# 608_donkey_030102_AllDirections.net
KiCad netlist of a schematic drawn in EAGLE
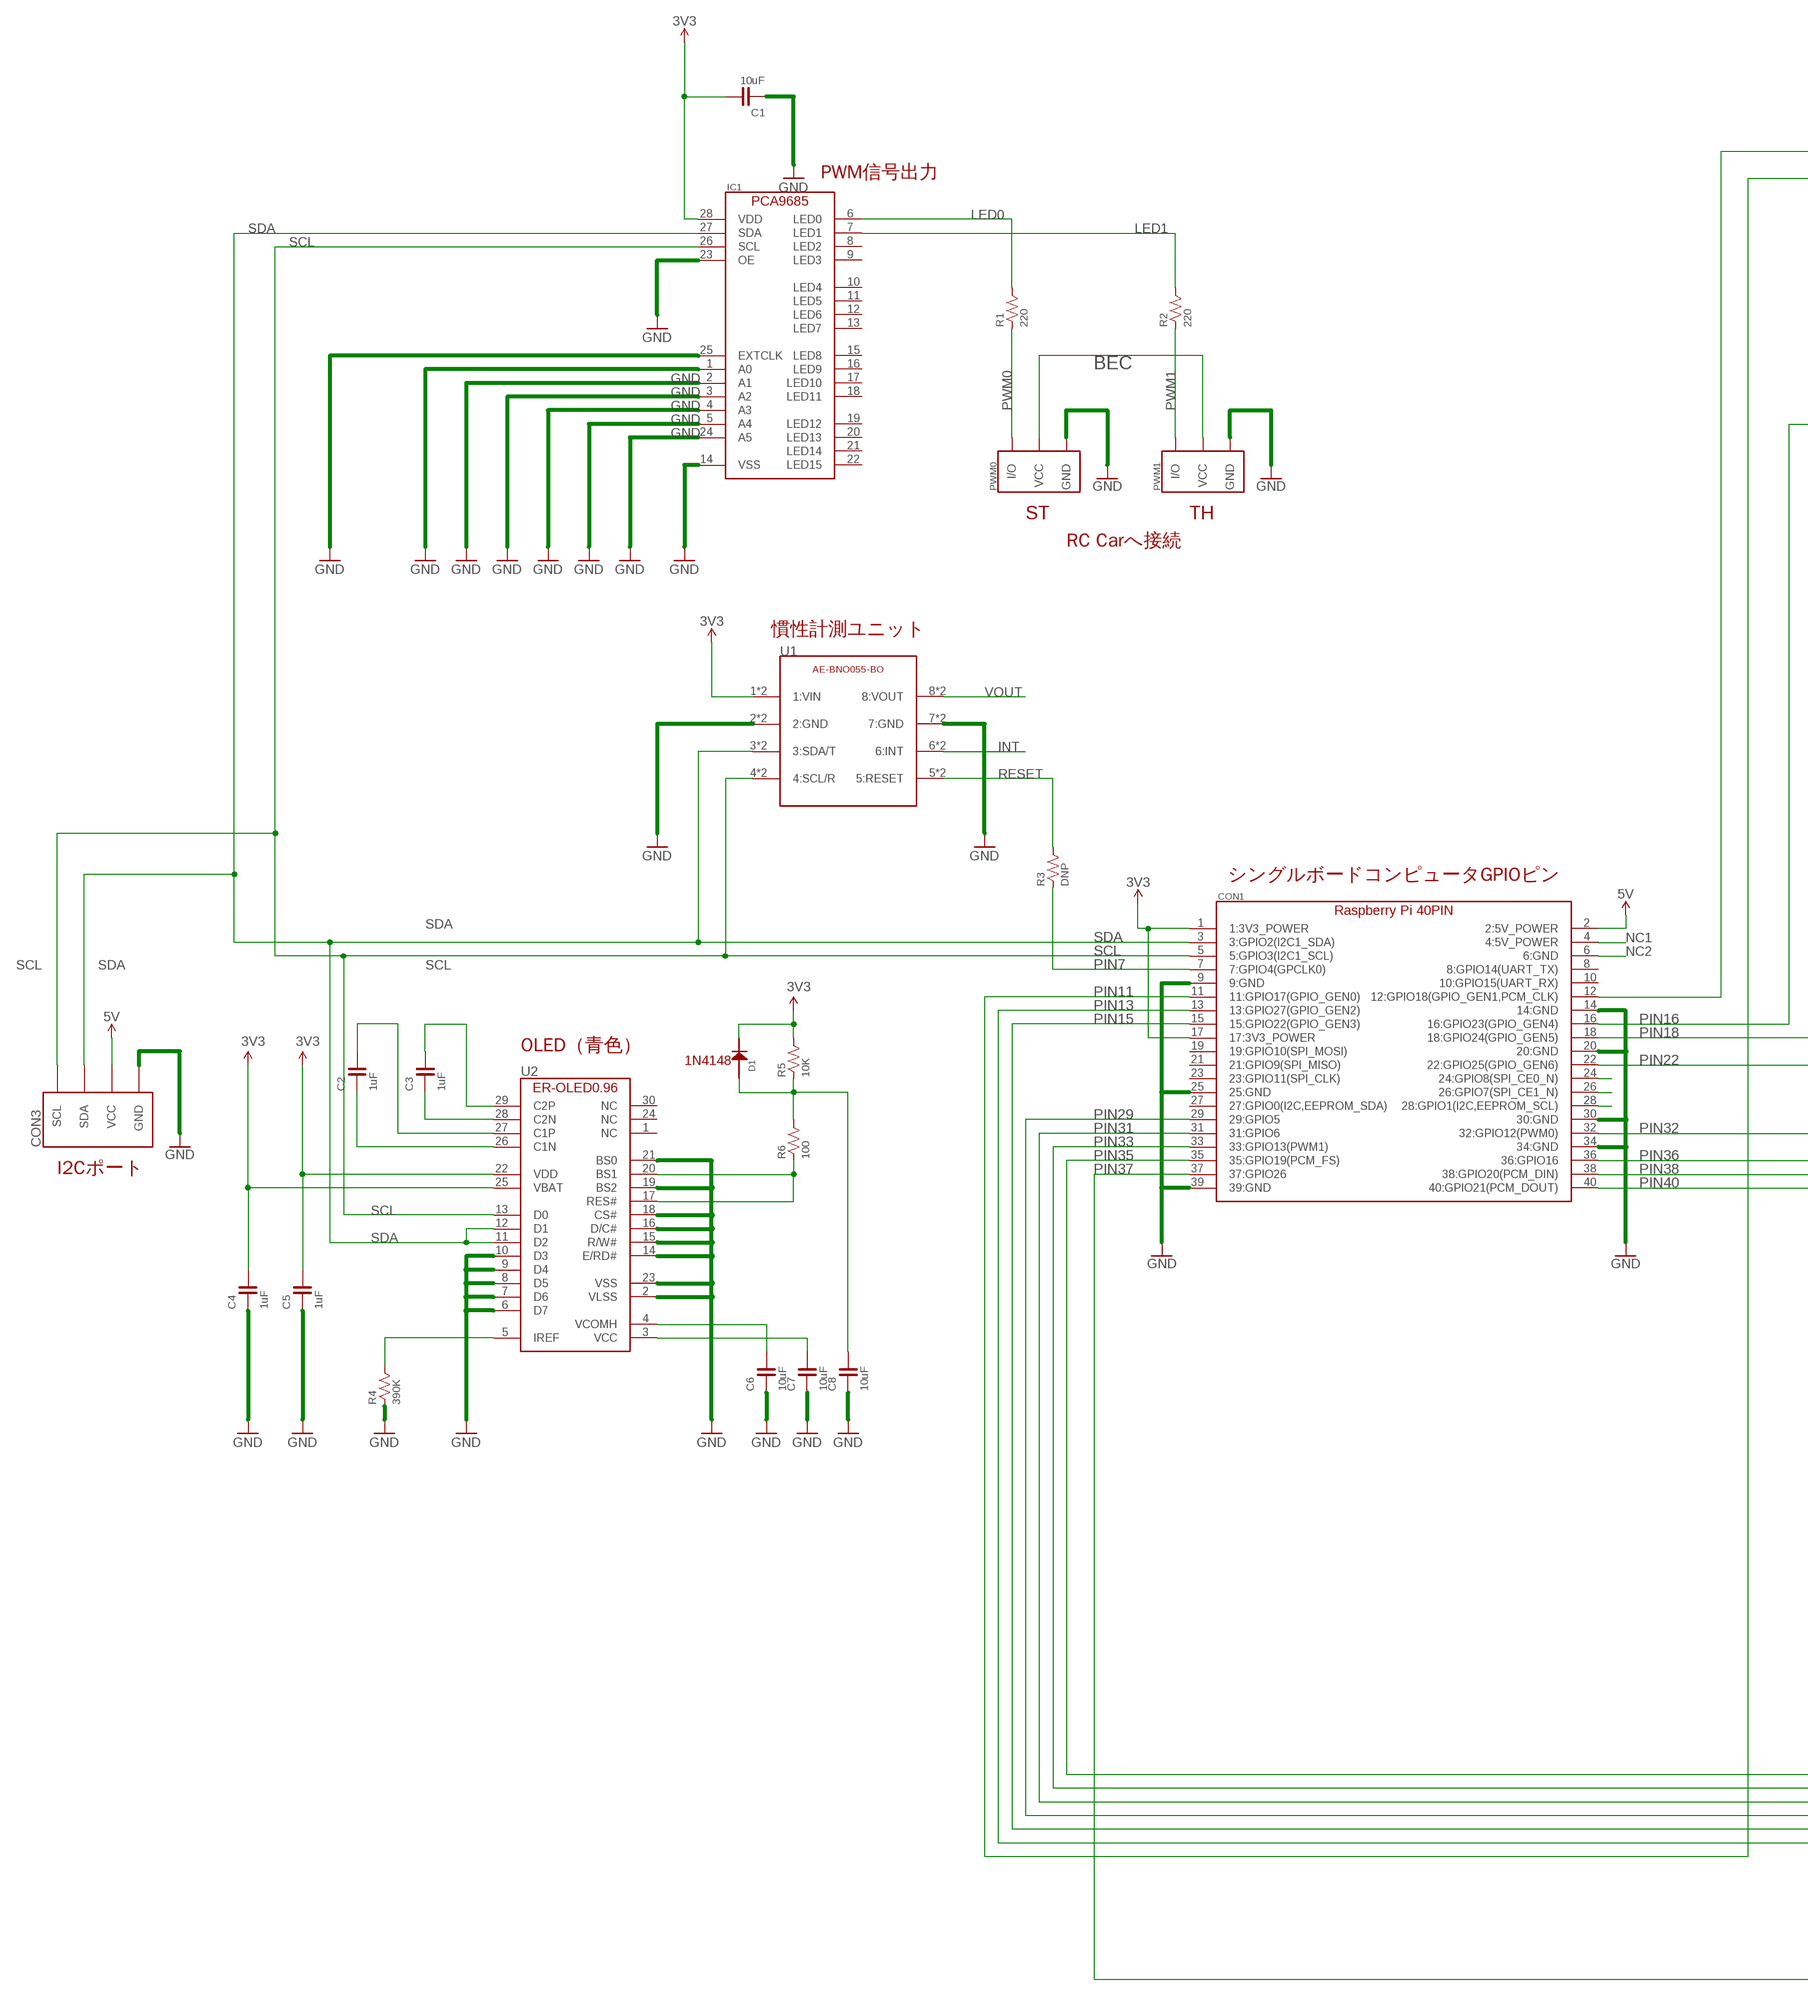
[diagram p0: schematic, sheet 1, part 1 of 3]
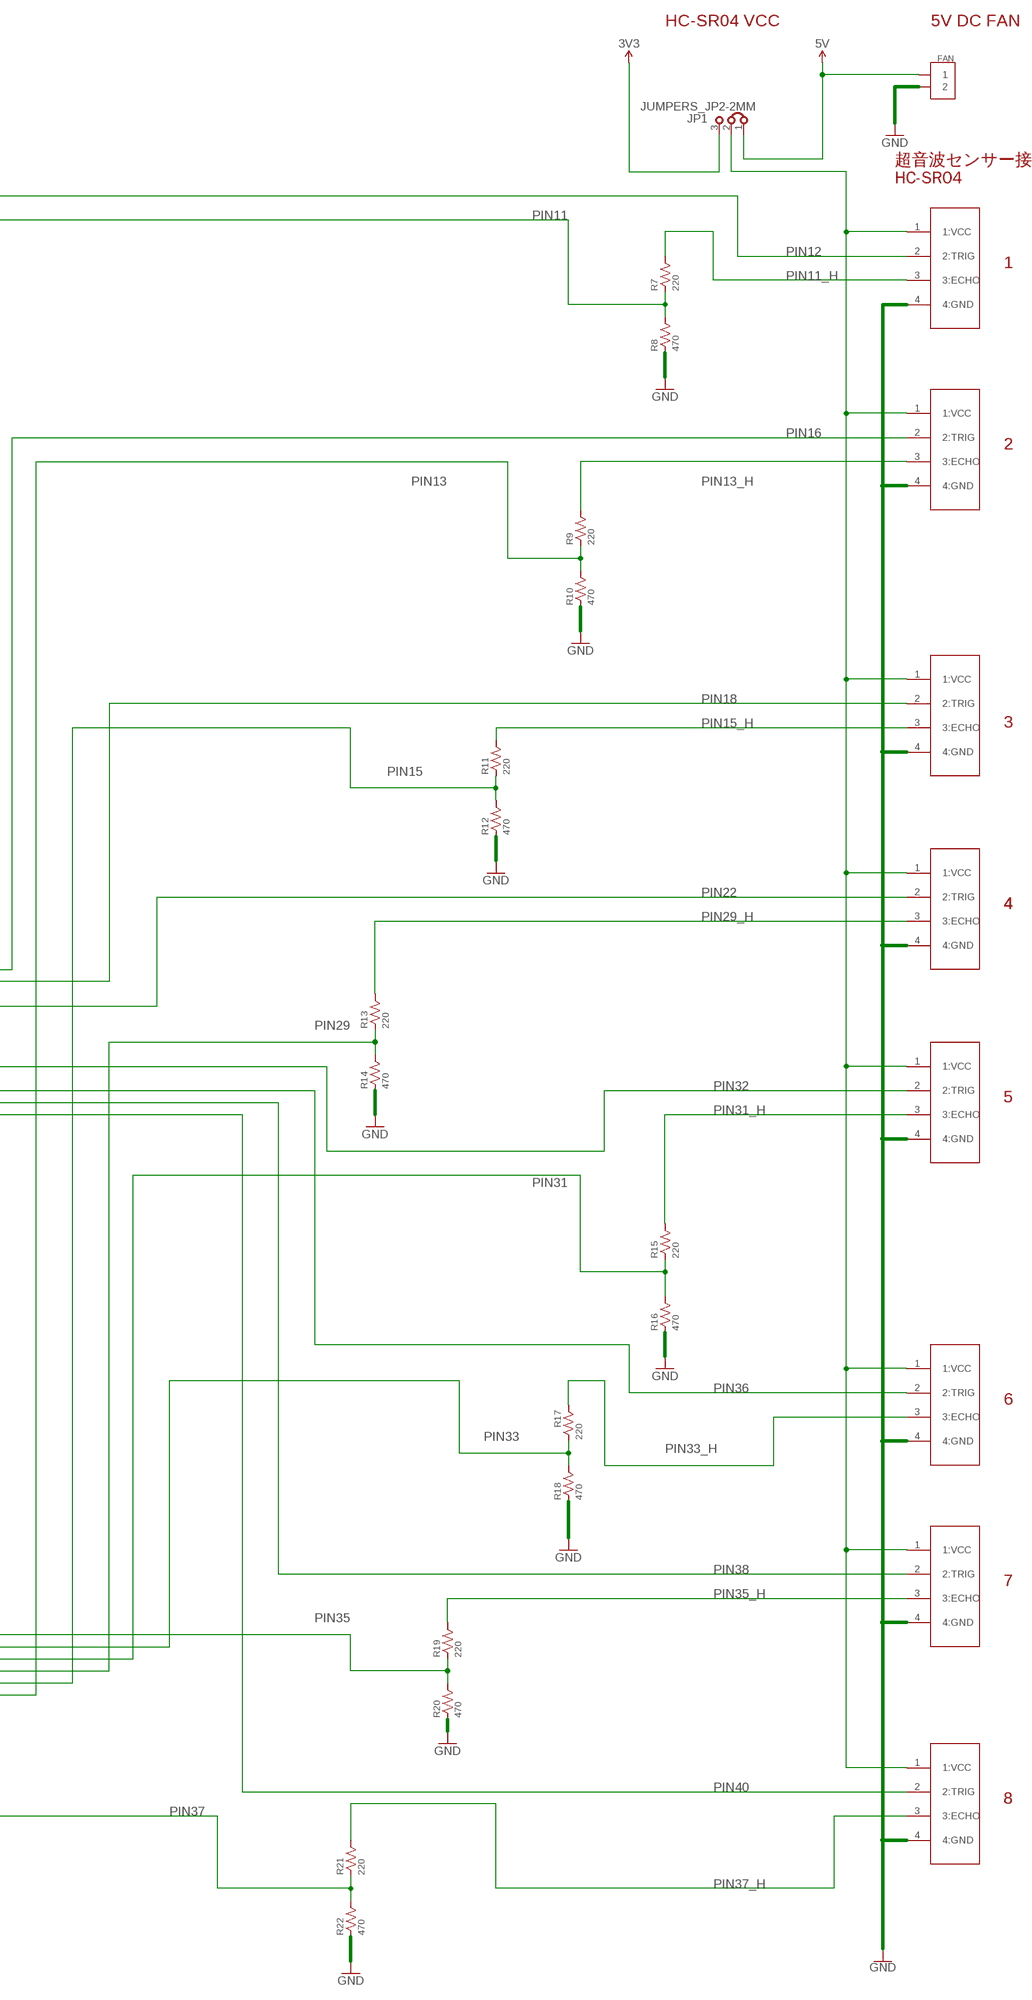
[diagram p1: schematic, sheet 1, part 2 of 3]
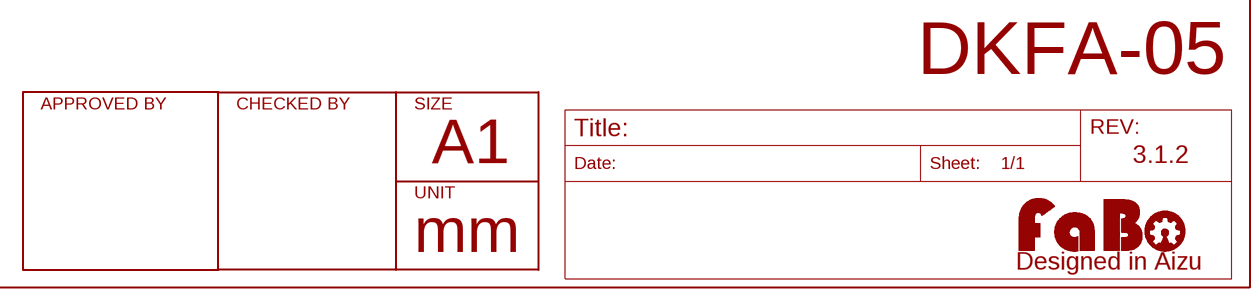
[diagram p2: schematic, sheet 1, part 3 of 3]

(export (version "E")
  (design (tool "Eeschema 10.0.6"))
  (components
    (comp (ref "C1")
      (value "10uF")
      (footprint "eagle-import:0603")
      (libsource (lib "eagle-import") (part "CAPACITOR-0603"))
    )
    (comp (ref "C2")
      (value "1uF")
      (footprint "eagle-import:0603-BOTTOM")
      (libsource (lib "eagle-import") (part "CAPACITOR-0603-BOTTOM"))
    )
    (comp (ref "C3")
      (value "1uF")
      (footprint "eagle-import:0603-BOTTOM")
      (libsource (lib "eagle-import") (part "CAPACITOR-0603-BOTTOM"))
    )
    (comp (ref "C4")
      (value "1uF")
      (footprint "eagle-import:0603-BOTTOM")
      (libsource (lib "eagle-import") (part "CAPACITOR-0603-BOTTOM"))
    )
    (comp (ref "C5")
      (value "1uF")
      (footprint "eagle-import:0603-BOTTOM")
      (libsource (lib "eagle-import") (part "CAPACITOR-0603-BOTTOM"))
    )
    (comp (ref "C6")
      (value "10uF")
      (footprint "eagle-import:0603-BOTTOM")
      (libsource (lib "eagle-import") (part "CAPACITOR-0603-BOTTOM"))
    )
    (comp (ref "C7")
      (value "10uF")
      (footprint "eagle-import:0603-BOTTOM")
      (libsource (lib "eagle-import") (part "CAPACITOR-0603-BOTTOM"))
    )
    (comp (ref "C8")
      (value "10uF")
      (footprint "eagle-import:0603-BOTTOM")
      (libsource (lib "eagle-import") (part "CAPACITOR-0603-BOTTOM"))
    )
    (comp (ref "CON1")
      (value "RASPBERRYPI_SHEILD")
      (footprint "eagle-import:RASPBERRY_PI_SHILED")
      (libsource (lib "eagle-import") (part "RASPBERRYPI_SHEILD"))
    )
    (comp (ref "CON3")
      (value "FABO_BRICK_I2C-S04B-PASK-2")
      (footprint "eagle-import:FABO_BRICK_I2C_S04B-PASK-2")
      (libsource (lib "eagle-import") (part "FABO_BRICK_I2C-S04B-PASK-2"))
    )
    (comp (ref "D1")
      (value "1N4148")
      (footprint "eagle-import:1N4148W")
      (libsource (lib "eagle-import") (part "1N4148"))
    )
    (comp (ref "FAN")
      (value "PIN_1X2")
      (footprint "eagle-import:PIN_1X2")
      (libsource (lib "eagle-import") (part "PIN_1X2"))
    )
    (comp (ref "HC1")
      (value "HC-SR04CONHS-SR04CON-SPEACING")
      (footprint "eagle-import:HC-SR04CON-SPEACE")
      (libsource (lib "eagle-import") (part "HC-SR04CONHS-SR04CON-SPEACING"))
    )
    (comp (ref "HC2")
      (value "HC-SR04CONHS-SR04CON-SPEACING")
      (footprint "eagle-import:HC-SR04CON-SPEACE")
      (libsource (lib "eagle-import") (part "HC-SR04CONHS-SR04CON-SPEACING"))
    )
    (comp (ref "HC3")
      (value "HC-SR04CONHS-SR04CON-SPEACING")
      (footprint "eagle-import:HC-SR04CON-SPEACE")
      (libsource (lib "eagle-import") (part "HC-SR04CONHS-SR04CON-SPEACING"))
    )
    (comp (ref "HC4")
      (value "HC-SR04CONHS-SR04CON-SPEACING")
      (footprint "eagle-import:HC-SR04CON-SPEACE")
      (libsource (lib "eagle-import") (part "HC-SR04CONHS-SR04CON-SPEACING"))
    )
    (comp (ref "HC5")
      (value "HC-SR04CONHS-SR04CON-SPEACING")
      (footprint "eagle-import:HC-SR04CON-SPEACE")
      (libsource (lib "eagle-import") (part "HC-SR04CONHS-SR04CON-SPEACING"))
    )
    (comp (ref "HC6")
      (value "HC-SR04CONHS-SR04CON-SPEACING")
      (footprint "eagle-import:HC-SR04CON-SPEACE")
      (libsource (lib "eagle-import") (part "HC-SR04CONHS-SR04CON-SPEACING"))
    )
    (comp (ref "HC7")
      (value "HC-SR04CONHS-SR04CON-SPEACING")
      (footprint "eagle-import:HC-SR04CON-SPEACE")
      (libsource (lib "eagle-import") (part "HC-SR04CONHS-SR04CON-SPEACING"))
    )
    (comp (ref "HC8")
      (value "HC-SR04CONHS-SR04CON-SPEACING")
      (footprint "eagle-import:HC-SR04CON-SPEACE")
      (libsource (lib "eagle-import") (part "HC-SR04CONHS-SR04CON-SPEACING"))
    )
    (comp (ref "IC1")
      (value "PCA9685BS")
      (footprint "eagle-import:PCA9685")
      (libsource (lib "eagle-import") (part "PCA9685BS"))
    )
    (comp (ref "JP1")
      (value "JUMPERS_JP2-2MM")
      (footprint "eagle-import:JUMPERS_JP2-2MM")
      (libsource (lib "eagle-import") (part "JUMPERS_JP2-2MM"))
    )
    (comp (ref "LOGO1")
      (value "LOGO_FABO-M")
      (footprint "eagle-import:LOGO_FABO_M")
      (libsource (lib "eagle-import") (part "LOGO_FABO-M"))
    )
    (comp (ref "PWM0")
      (value "PWM0")
      (footprint "eagle-import:PIN_1X3_NARROW")
      (libsource (lib "eagle-import") (part "FABO-BRICK-3PIN_HEADER"))
    )
    (comp (ref "PWM1")
      (value "PWM1")
      (footprint "eagle-import:PIN_1X3_NARROW")
      (libsource (lib "eagle-import") (part "FABO-BRICK-3PIN_HEADER"))
    )
    (comp (ref "R1")
      (value "220")
      (footprint "eagle-import:0603")
      (libsource (lib "eagle-import") (part "RESISTOR-0603"))
    )
    (comp (ref "R2")
      (value "220")
      (footprint "eagle-import:0603")
      (libsource (lib "eagle-import") (part "RESISTOR-0603"))
    )
    (comp (ref "R3")
      (value "DNP")
      (footprint "eagle-import:0603-BOTTOM")
      (libsource (lib "eagle-import") (part "RESISTOR-0603-BOTTOM"))
    )
    (comp (ref "R4")
      (value "390K")
      (footprint "eagle-import:0603-BOTTOM")
      (libsource (lib "eagle-import") (part "RESISTOR-0603-BOTTOM"))
    )
    (comp (ref "R5")
      (value "10K")
      (footprint "eagle-import:0603-BOTTOM")
      (libsource (lib "eagle-import") (part "RESISTOR-0603-BOTTOM"))
    )
    (comp (ref "R6")
      (value "100")
      (footprint "eagle-import:0603-BOTTOM")
      (libsource (lib "eagle-import") (part "RESISTOR-0603-BOTTOM"))
    )
    (comp (ref "R7")
      (value "220")
      (footprint "eagle-import:0603")
      (libsource (lib "eagle-import") (part "RESISTOR-0603"))
    )
    (comp (ref "R8")
      (value "470")
      (footprint "eagle-import:0603")
      (libsource (lib "eagle-import") (part "RESISTOR-0603"))
    )
    (comp (ref "R9")
      (value "220")
      (footprint "eagle-import:0603")
      (libsource (lib "eagle-import") (part "RESISTOR-0603"))
    )
    (comp (ref "R10")
      (value "470")
      (footprint "eagle-import:0603")
      (libsource (lib "eagle-import") (part "RESISTOR-0603"))
    )
    (comp (ref "R11")
      (value "220")
      (footprint "eagle-import:0603")
      (libsource (lib "eagle-import") (part "RESISTOR-0603"))
    )
    (comp (ref "R12")
      (value "470")
      (footprint "eagle-import:0603")
      (libsource (lib "eagle-import") (part "RESISTOR-0603"))
    )
    (comp (ref "R13")
      (value "220")
      (footprint "eagle-import:0603")
      (libsource (lib "eagle-import") (part "RESISTOR-0603"))
    )
    (comp (ref "R14")
      (value "470")
      (footprint "eagle-import:0603")
      (libsource (lib "eagle-import") (part "RESISTOR-0603"))
    )
    (comp (ref "R15")
      (value "220")
      (footprint "eagle-import:0603")
      (libsource (lib "eagle-import") (part "RESISTOR-0603"))
    )
    (comp (ref "R16")
      (value "470")
      (footprint "eagle-import:0603")
      (libsource (lib "eagle-import") (part "RESISTOR-0603"))
    )
    (comp (ref "R17")
      (value "220")
      (footprint "eagle-import:0603")
      (libsource (lib "eagle-import") (part "RESISTOR-0603"))
    )
    (comp (ref "R18")
      (value "470")
      (footprint "eagle-import:0603")
      (libsource (lib "eagle-import") (part "RESISTOR-0603"))
    )
    (comp (ref "R19")
      (value "220")
      (footprint "eagle-import:0603")
      (libsource (lib "eagle-import") (part "RESISTOR-0603"))
    )
    (comp (ref "R20")
      (value "470")
      (footprint "eagle-import:0603")
      (libsource (lib "eagle-import") (part "RESISTOR-0603"))
    )
    (comp (ref "R21")
      (value "220")
      (footprint "eagle-import:0603")
      (libsource (lib "eagle-import") (part "RESISTOR-0603"))
    )
    (comp (ref "R22")
      (value "470")
      (footprint "eagle-import:0603")
      (libsource (lib "eagle-import") (part "RESISTOR-0603"))
    )
    (comp (ref "U1")
      (value "AE-BNO055-BO")
      (footprint "eagle-import:DIP_8")
      (libsource (lib "eagle-import") (part "AE-BNO055-BO"))
    )
    (comp (ref "U2")
      (value "ER-OLED0.96-1ER-CON30HT-1_REV2")
      (footprint "eagle-import:ER-CON30HT-1_REV2")
      (libsource (lib "eagle-import") (part "ER-OLED0.96-1ER-CON30HT-1_REV2"))
    )
  )
  (nets
    (net (code "1") (name "/BEC") (class "Default")
      (node (ref "PWM0") (pin "2") (pinfunction "VCC_2") (pintype "bidirectional"))
      (node (ref "PWM1") (pin "2") (pinfunction "VCC_2") (pintype "bidirectional"))
    )
    (net (code "2") (name "/INT") (class "Default")
      (node (ref "U1") (pin "6") (pinfunction "6:INT_6") (pintype "output"))
      (node (ref "U1") (pin "6-1") (pinfunction "6:INT_6-1") (pintype "output"))
    )
    (net (code "3") (name "/LED0") (class "Default")
      (node (ref "IC1") (pin "6") (pinfunction "LED0_6") (pintype "bidirectional"))
      (node (ref "R1") (pin "2") (pinfunction "2_2") (pintype "bidirectional"))
    )
    (net (code "4") (name "/LED1") (class "Default")
      (node (ref "IC1") (pin "7") (pinfunction "LED1_7") (pintype "bidirectional"))
      (node (ref "R2") (pin "2") (pinfunction "2_2") (pintype "bidirectional"))
    )
    (net (code "5") (name "/NC1") (class "Default")
      (node (ref "CON1") (pin "4") (pinfunction "4:5V_POWER_4") (pintype "power_in"))
    )
    (net (code "6") (name "/NC2") (class "Default")
      (node (ref "CON1") (pin "6") (pinfunction "6:GND_6") (pintype "power_in"))
    )
    (net (code "7") (name "/PIN7") (class "Default")
      (node (ref "CON1") (pin "7") (pinfunction "7:GPIO4(GPCLK0)_7") (pintype "bidirectional"))
      (node (ref "R3") (pin "1") (pinfunction "1_1") (pintype "bidirectional"))
    )
    (net (code "8") (name "/PIN11") (class "Default")
      (node (ref "CON1") (pin "11") (pinfunction "11:GPIO17(GPIO_GEN0)_11") (pintype "bidirectional"))
      (node (ref "R7") (pin "1") (pinfunction "1_1") (pintype "bidirectional"))
      (node (ref "R8") (pin "2") (pinfunction "2_2") (pintype "bidirectional"))
    )
    (net (code "9") (name "/PIN11_H") (class "Default")
      (node (ref "HC1") (pin "3") (pinfunction "3:ECHO_3") (pintype "bidirectional"))
      (node (ref "R7") (pin "2") (pinfunction "2_2") (pintype "bidirectional"))
    )
    (net (code "10") (name "/PIN12") (class "Default")
      (node (ref "CON1") (pin "12") (pinfunction "12:GPIO18(GPIO_GEN1,PCM_CLK)_12") (pintype "bidirectional"))
      (node (ref "HC1") (pin "2") (pinfunction "2:TRIG_2") (pintype "bidirectional"))
    )
    (net (code "11") (name "/PIN13") (class "Default")
      (node (ref "CON1") (pin "13") (pinfunction "13:GPIO27(GPIO_GEN2)_13") (pintype "bidirectional"))
      (node (ref "R10") (pin "2") (pinfunction "2_2") (pintype "bidirectional"))
      (node (ref "R9") (pin "1") (pinfunction "1_1") (pintype "bidirectional"))
    )
    (net (code "12") (name "/PIN13_H") (class "Default")
      (node (ref "HC2") (pin "3") (pinfunction "3:ECHO_3") (pintype "bidirectional"))
      (node (ref "R9") (pin "2") (pinfunction "2_2") (pintype "bidirectional"))
    )
    (net (code "13") (name "/PIN15") (class "Default")
      (node (ref "CON1") (pin "15") (pinfunction "15:GPIO22(GPIO_GEN3)_15") (pintype "bidirectional"))
      (node (ref "R11") (pin "1") (pinfunction "1_1") (pintype "bidirectional"))
      (node (ref "R12") (pin "2") (pinfunction "2_2") (pintype "bidirectional"))
    )
    (net (code "14") (name "/PIN15_H") (class "Default")
      (node (ref "HC3") (pin "3") (pinfunction "3:ECHO_3") (pintype "bidirectional"))
      (node (ref "R11") (pin "2") (pinfunction "2_2") (pintype "bidirectional"))
    )
    (net (code "15") (name "/PIN16") (class "Default")
      (node (ref "CON1") (pin "16") (pinfunction "16:GPIO23(GPIO_GEN4)_16") (pintype "bidirectional"))
      (node (ref "HC2") (pin "2") (pinfunction "2:TRIG_2") (pintype "bidirectional"))
    )
    (net (code "16") (name "/PIN18") (class "Default")
      (node (ref "CON1") (pin "18") (pinfunction "18:GPIO24(GPIO_GEN5)_18") (pintype "bidirectional"))
      (node (ref "HC3") (pin "2") (pinfunction "2:TRIG_2") (pintype "bidirectional"))
    )
    (net (code "17") (name "/PIN22") (class "Default")
      (node (ref "CON1") (pin "22") (pinfunction "22:GPIO25(GPIO_GEN6)_22") (pintype "bidirectional"))
      (node (ref "HC4") (pin "2") (pinfunction "2:TRIG_2") (pintype "bidirectional"))
    )
    (net (code "18") (name "/PIN29") (class "Default")
      (node (ref "CON1") (pin "29") (pinfunction "29:GPIO5_29") (pintype "bidirectional"))
      (node (ref "R13") (pin "1") (pinfunction "1_1") (pintype "bidirectional"))
      (node (ref "R14") (pin "2") (pinfunction "2_2") (pintype "bidirectional"))
    )
    (net (code "19") (name "/PIN29_H") (class "Default")
      (node (ref "HC4") (pin "3") (pinfunction "3:ECHO_3") (pintype "bidirectional"))
      (node (ref "R13") (pin "2") (pinfunction "2_2") (pintype "bidirectional"))
    )
    (net (code "20") (name "/PIN31") (class "Default")
      (node (ref "CON1") (pin "31") (pinfunction "31:GPIO6_31") (pintype "bidirectional"))
      (node (ref "R15") (pin "1") (pinfunction "1_1") (pintype "bidirectional"))
      (node (ref "R16") (pin "2") (pinfunction "2_2") (pintype "bidirectional"))
    )
    (net (code "21") (name "/PIN31_H") (class "Default")
      (node (ref "HC5") (pin "3") (pinfunction "3:ECHO_3") (pintype "bidirectional"))
      (node (ref "R15") (pin "2") (pinfunction "2_2") (pintype "bidirectional"))
    )
    (net (code "22") (name "/PIN32") (class "Default")
      (node (ref "CON1") (pin "32") (pinfunction "32:GPIO12(PWM0)_32") (pintype "bidirectional"))
      (node (ref "HC5") (pin "2") (pinfunction "2:TRIG_2") (pintype "bidirectional"))
    )
    (net (code "23") (name "/PIN33") (class "Default")
      (node (ref "CON1") (pin "33") (pinfunction "33:GPIO13(PWM1)_33") (pintype "bidirectional"))
      (node (ref "R17") (pin "1") (pinfunction "1_1") (pintype "bidirectional"))
      (node (ref "R18") (pin "2") (pinfunction "2_2") (pintype "bidirectional"))
    )
    (net (code "24") (name "/PIN33_H") (class "Default")
      (node (ref "HC6") (pin "3") (pinfunction "3:ECHO_3") (pintype "bidirectional"))
      (node (ref "R17") (pin "2") (pinfunction "2_2") (pintype "bidirectional"))
    )
    (net (code "25") (name "/PIN35") (class "Default")
      (node (ref "CON1") (pin "35") (pinfunction "35:GPIO19(PCM_FS)_35") (pintype "bidirectional"))
      (node (ref "R19") (pin "1") (pinfunction "1_1") (pintype "bidirectional"))
      (node (ref "R20") (pin "2") (pinfunction "2_2") (pintype "bidirectional"))
    )
    (net (code "26") (name "/PIN35_H") (class "Default")
      (node (ref "HC7") (pin "3") (pinfunction "3:ECHO_3") (pintype "bidirectional"))
      (node (ref "R19") (pin "2") (pinfunction "2_2") (pintype "bidirectional"))
    )
    (net (code "27") (name "/PIN36") (class "Default")
      (node (ref "CON1") (pin "36") (pinfunction "36:GPIO16_36") (pintype "bidirectional"))
      (node (ref "HC6") (pin "2") (pinfunction "2:TRIG_2") (pintype "bidirectional"))
    )
    (net (code "28") (name "/PIN37") (class "Default")
      (node (ref "CON1") (pin "37") (pinfunction "37:GPIO26_37") (pintype "bidirectional"))
      (node (ref "R21") (pin "1") (pinfunction "1_1") (pintype "bidirectional"))
      (node (ref "R22") (pin "2") (pinfunction "2_2") (pintype "bidirectional"))
    )
    (net (code "29") (name "/PIN37_H") (class "Default")
      (node (ref "HC8") (pin "3") (pinfunction "3:ECHO_3") (pintype "bidirectional"))
      (node (ref "R21") (pin "2") (pinfunction "2_2") (pintype "bidirectional"))
    )
    (net (code "30") (name "/PIN38") (class "Default")
      (node (ref "CON1") (pin "38") (pinfunction "38:GPIO20(PCM_DIN)_38") (pintype "bidirectional"))
      (node (ref "HC7") (pin "2") (pinfunction "2:TRIG_2") (pintype "bidirectional"))
    )
    (net (code "31") (name "/PIN40") (class "Default")
      (node (ref "CON1") (pin "40") (pinfunction "40:GPIO21(PCM_DOUT)_40") (pintype "bidirectional"))
      (node (ref "HC8") (pin "2") (pinfunction "2:TRIG_2") (pintype "bidirectional"))
    )
    (net (code "32") (name "/PWM0") (class "Default")
      (node (ref "PWM0") (pin "1") (pinfunction "I/O_1") (pintype "bidirectional"))
      (node (ref "R1") (pin "1") (pinfunction "1_1") (pintype "bidirectional"))
    )
    (net (code "33") (name "/PWM1") (class "Default")
      (node (ref "PWM1") (pin "1") (pinfunction "I/O_1") (pintype "bidirectional"))
      (node (ref "R2") (pin "1") (pinfunction "1_1") (pintype "bidirectional"))
    )
    (net (code "34") (name "/RESET") (class "Default")
      (node (ref "R3") (pin "2") (pinfunction "2_2") (pintype "bidirectional"))
      (node (ref "U1") (pin "5") (pinfunction "5:RESET_5") (pintype "input"))
      (node (ref "U1") (pin "5-1") (pinfunction "5:RESET_5-1") (pintype "input"))
    )
    (net (code "35") (name "/SCL") (class "Default")
      (node (ref "CON1") (pin "5") (pinfunction "5:GPIO3(I2C1_SCL)_5") (pintype "bidirectional"))
      (node (ref "CON3") (pin "SCL") (pinfunction "SCL_SCL") (pintype "bidirectional"))
      (node (ref "IC1") (pin "26") (pinfunction "SCL_26") (pintype "bidirectional"))
      (node (ref "U1") (pin "4") (pinfunction "4:SCL/R_4") (pintype "bidirectional"))
      (node (ref "U1") (pin "4-1") (pinfunction "4:SCL/R_4-1") (pintype "bidirectional"))
      (node (ref "U2") (pin "13") (pinfunction "D0_13") (pintype "bidirectional"))
    )
    (net (code "36") (name "/SDA") (class "Default")
      (node (ref "CON1") (pin "3") (pinfunction "3:GPIO2(I2C1_SDA)_3") (pintype "bidirectional"))
      (node (ref "CON3") (pin "SDA") (pinfunction "SDA_SDA") (pintype "bidirectional"))
      (node (ref "IC1") (pin "27") (pinfunction "SDA_27") (pintype "bidirectional"))
      (node (ref "U1") (pin "3") (pinfunction "3:SDA/T_3") (pintype "bidirectional"))
      (node (ref "U1") (pin "3-1") (pinfunction "3:SDA/T_3-1") (pintype "bidirectional"))
      (node (ref "U2") (pin "11") (pinfunction "D2_11") (pintype "bidirectional"))
      (node (ref "U2") (pin "12") (pinfunction "D1_12") (pintype "bidirectional"))
    )
    (net (code "37") (name "/VOUT") (class "Default")
      (node (ref "U1") (pin "8") (pinfunction "8:VOUT_8") (pintype "power_in"))
      (node (ref "U1") (pin "8-1") (pinfunction "8:VOUT_8-1") (pintype "power_in"))
    )
    (net (code "38") (name "3V3") (class "Default")
      (node (ref "C1") (pin "2") (pinfunction "2_2") (pintype "passive"))
      (node (ref "C4") (pin "2") (pinfunction "2_2") (pintype "passive"))
      (node (ref "C5") (pin "2") (pinfunction "2_2") (pintype "passive"))
      (node (ref "CON1") (pin "1") (pinfunction "1:3V3_POWER_1") (pintype "power_in"))
      (node (ref "CON1") (pin "17") (pinfunction "17:3V3_POWER_17") (pintype "power_in"))
      (node (ref "D1") (pin "CATHODE") (pinfunction "CATHODE_CATHODE") (pintype "bidirectional"))
      (node (ref "IC1") (pin "28") (pinfunction "VDD_28") (pintype "bidirectional"))
      (node (ref "JP1") (pin "3") (pinfunction "3_3") (pintype "passive"))
      (node (ref "R5") (pin "2") (pinfunction "2_2") (pintype "bidirectional"))
      (node (ref "U1") (pin "1") (pinfunction "1:VIN_1") (pintype "power_in"))
      (node (ref "U1") (pin "1-1") (pinfunction "1:VIN_1-1") (pintype "power_in"))
      (node (ref "U2") (pin "22") (pinfunction "VDD_22") (pintype "bidirectional"))
      (node (ref "U2") (pin "25") (pinfunction "VBAT_25") (pintype "bidirectional"))
    )
    (net (code "39") (name "5V") (class "Default")
      (node (ref "CON1") (pin "2") (pinfunction "2:5V_POWER_2") (pintype "power_in"))
      (node (ref "CON3") (pin "VCC") (pinfunction "VCC_VCC") (pintype "bidirectional"))
      (node (ref "FAN") (pin "1") (pinfunction "1_1") (pintype "bidirectional"))
      (node (ref "JP1") (pin "1") (pinfunction "1_1") (pintype "passive"))
    )
    (net (code "40") (name "GND") (class "Default")
      (node (ref "C1") (pin "1") (pinfunction "1_1") (pintype "passive"))
      (node (ref "C4") (pin "1") (pinfunction "1_1") (pintype "passive"))
      (node (ref "C5") (pin "1") (pinfunction "1_1") (pintype "passive"))
      (node (ref "C6") (pin "1") (pinfunction "1_1") (pintype "passive"))
      (node (ref "C7") (pin "1") (pinfunction "1_1") (pintype "passive"))
      (node (ref "C8") (pin "1") (pinfunction "1_1") (pintype "passive"))
      (node (ref "CON1") (pin "14") (pinfunction "14:GND_14") (pintype "power_in"))
      (node (ref "CON1") (pin "20") (pinfunction "20:GND_20") (pintype "power_in"))
      (node (ref "CON1") (pin "25") (pinfunction "25:GND_25") (pintype "power_in"))
      (node (ref "CON1") (pin "30") (pinfunction "30:GND_30") (pintype "power_in"))
      (node (ref "CON1") (pin "34") (pinfunction "34:GND_34") (pintype "power_in"))
      (node (ref "CON1") (pin "39") (pinfunction "39:GND_39") (pintype "power_in"))
      (node (ref "CON1") (pin "9") (pinfunction "9:GND_9") (pintype "power_in"))
      (node (ref "CON3") (pin "GND") (pinfunction "GND_GND") (pintype "bidirectional"))
      (node (ref "FAN") (pin "2") (pinfunction "2_2") (pintype "bidirectional"))
      (node (ref "HC1") (pin "4") (pinfunction "4:GND_4") (pintype "bidirectional"))
      (node (ref "HC2") (pin "4") (pinfunction "4:GND_4") (pintype "bidirectional"))
      (node (ref "HC3") (pin "4") (pinfunction "4:GND_4") (pintype "bidirectional"))
      (node (ref "HC4") (pin "4") (pinfunction "4:GND_4") (pintype "bidirectional"))
      (node (ref "HC5") (pin "4") (pinfunction "4:GND_4") (pintype "bidirectional"))
      (node (ref "HC6") (pin "4") (pinfunction "4:GND_4") (pintype "bidirectional"))
      (node (ref "HC7") (pin "4") (pinfunction "4:GND_4") (pintype "bidirectional"))
      (node (ref "HC8") (pin "4") (pinfunction "4:GND_4") (pintype "bidirectional"))
      (node (ref "IC1") (pin "1") (pinfunction "A0_1") (pintype "bidirectional"))
      (node (ref "IC1") (pin "14") (pinfunction "VSS_14") (pintype "bidirectional"))
      (node (ref "IC1") (pin "2") (pinfunction "A1_2") (pintype "bidirectional"))
      (node (ref "IC1") (pin "23") (pinfunction "OE_23") (pintype "bidirectional"))
      (node (ref "IC1") (pin "24") (pinfunction "A5_24") (pintype "bidirectional"))
      (node (ref "IC1") (pin "25") (pinfunction "EXTCLK_25") (pintype "bidirectional"))
      (node (ref "IC1") (pin "3") (pinfunction "A2_3") (pintype "bidirectional"))
      (node (ref "IC1") (pin "4") (pinfunction "A3_4") (pintype "bidirectional"))
      (node (ref "IC1") (pin "5") (pinfunction "A4_5") (pintype "bidirectional"))
      (node (ref "PWM0") (pin "3") (pinfunction "GND_3") (pintype "bidirectional"))
      (node (ref "PWM1") (pin "3") (pinfunction "GND_3") (pintype "bidirectional"))
      (node (ref "R10") (pin "1") (pinfunction "1_1") (pintype "bidirectional"))
      (node (ref "R12") (pin "1") (pinfunction "1_1") (pintype "bidirectional"))
      (node (ref "R14") (pin "1") (pinfunction "1_1") (pintype "bidirectional"))
      (node (ref "R16") (pin "1") (pinfunction "1_1") (pintype "bidirectional"))
      (node (ref "R18") (pin "1") (pinfunction "1_1") (pintype "bidirectional"))
      (node (ref "R20") (pin "1") (pinfunction "1_1") (pintype "bidirectional"))
      (node (ref "R22") (pin "1") (pinfunction "1_1") (pintype "bidirectional"))
      (node (ref "R4") (pin "1") (pinfunction "1_1") (pintype "bidirectional"))
      (node (ref "R8") (pin "1") (pinfunction "1_1") (pintype "bidirectional"))
      (node (ref "U1") (pin "2") (pinfunction "2:GND_2") (pintype "power_in"))
      (node (ref "U1") (pin "2-1") (pinfunction "2:GND_2-1") (pintype "power_in"))
      (node (ref "U1") (pin "7") (pinfunction "7:GND_7") (pintype "power_in"))
      (node (ref "U1") (pin "7-1") (pinfunction "7:GND_7-1") (pintype "power_in"))
      (node (ref "U2") (pin "10") (pinfunction "D3_10") (pintype "bidirectional"))
      (node (ref "U2") (pin "14") (pinfunction "E/RD#_14") (pintype "bidirectional"))
      (node (ref "U2") (pin "15") (pinfunction "R/W#_15") (pintype "bidirectional"))
      (node (ref "U2") (pin "16") (pinfunction "D/C#_16") (pintype "bidirectional"))
      (node (ref "U2") (pin "18") (pinfunction "CS#_18") (pintype "bidirectional"))
      (node (ref "U2") (pin "19") (pinfunction "BS2_19") (pintype "bidirectional"))
      (node (ref "U2") (pin "2") (pinfunction "VLSS_2") (pintype "bidirectional"))
      (node (ref "U2") (pin "21") (pinfunction "BS0_21") (pintype "bidirectional"))
      (node (ref "U2") (pin "23") (pinfunction "VSS_23") (pintype "bidirectional"))
      (node (ref "U2") (pin "6") (pinfunction "D7_6") (pintype "bidirectional"))
      (node (ref "U2") (pin "7") (pinfunction "D6_7") (pintype "bidirectional"))
      (node (ref "U2") (pin "8") (pinfunction "D5_8") (pintype "bidirectional"))
      (node (ref "U2") (pin "9") (pinfunction "D4_9") (pintype "bidirectional"))
    )
    (net (code "41") (name "Net-(C8-Pad2)") (class "Default")
      (node (ref "C8") (pin "2") (pinfunction "2_2") (pintype "passive"))
      (node (ref "D1") (pin "ANODE") (pinfunction "ANODE_ANODE") (pintype "bidirectional"))
      (node (ref "R5") (pin "1") (pinfunction "1_1") (pintype "bidirectional"))
      (node (ref "R6") (pin "2") (pinfunction "2_2") (pintype "bidirectional"))
    )
    (net (code "42") (name "Net-(HC1-1:VCC)") (class "Default")
      (node (ref "HC1") (pin "1") (pinfunction "1:VCC_1") (pintype "bidirectional"))
      (node (ref "HC2") (pin "1") (pinfunction "1:VCC_1") (pintype "bidirectional"))
      (node (ref "HC3") (pin "1") (pinfunction "1:VCC_1") (pintype "bidirectional"))
      (node (ref "HC4") (pin "1") (pinfunction "1:VCC_1") (pintype "bidirectional"))
      (node (ref "HC5") (pin "1") (pinfunction "1:VCC_1") (pintype "bidirectional"))
      (node (ref "HC6") (pin "1") (pinfunction "1:VCC_1") (pintype "bidirectional"))
      (node (ref "HC7") (pin "1") (pinfunction "1:VCC_1") (pintype "bidirectional"))
      (node (ref "HC8") (pin "1") (pinfunction "1:VCC_1") (pintype "bidirectional"))
      (node (ref "JP1") (pin "2") (pinfunction "2_2") (pintype "passive"))
    )
    (net (code "43") (name "Net-(U2-BS1)") (class "Default")
      (node (ref "R6") (pin "1") (pinfunction "1_1") (pintype "bidirectional"))
      (node (ref "U2") (pin "17") (pinfunction "RES#_17") (pintype "bidirectional"))
      (node (ref "U2") (pin "20") (pinfunction "BS1_20") (pintype "bidirectional"))
    )
    (net (code "44") (name "Net-(U2-C1N)") (class "Default")
      (node (ref "C2") (pin "1") (pinfunction "1_1") (pintype "passive"))
      (node (ref "U2") (pin "26") (pinfunction "C1N_26") (pintype "bidirectional"))
    )
    (net (code "45") (name "Net-(U2-C1P)") (class "Default")
      (node (ref "C2") (pin "2") (pinfunction "2_2") (pintype "passive"))
      (node (ref "U2") (pin "27") (pinfunction "C1P_27") (pintype "bidirectional"))
    )
    (net (code "46") (name "Net-(U2-C2N)") (class "Default")
      (node (ref "C3") (pin "1") (pinfunction "1_1") (pintype "passive"))
      (node (ref "U2") (pin "28") (pinfunction "C2N_28") (pintype "bidirectional"))
    )
    (net (code "47") (name "Net-(U2-C2P)") (class "Default")
      (node (ref "C3") (pin "2") (pinfunction "2_2") (pintype "passive"))
      (node (ref "U2") (pin "29") (pinfunction "C2P_29") (pintype "bidirectional"))
    )
    (net (code "48") (name "Net-(U2-IREF)") (class "Default")
      (node (ref "R4") (pin "2") (pinfunction "2_2") (pintype "bidirectional"))
      (node (ref "U2") (pin "5") (pinfunction "IREF_5") (pintype "bidirectional"))
    )
    (net (code "49") (name "Net-(U2-VCC)") (class "Default")
      (node (ref "C7") (pin "2") (pinfunction "2_2") (pintype "passive"))
      (node (ref "U2") (pin "3") (pinfunction "VCC_3") (pintype "bidirectional"))
    )
    (net (code "50") (name "Net-(U2-VCOMH)") (class "Default")
      (node (ref "C6") (pin "2") (pinfunction "2_2") (pintype "passive"))
      (node (ref "U2") (pin "4") (pinfunction "VCOMH_4") (pintype "bidirectional"))
    )
    (net (code "51") (name "unconnected-(CON1-8:GPIO14(UART_TX)-Pad8)") (class "Default")
      (node (ref "CON1") (pin "8") (pinfunction "8:GPIO14(UART_TX)_8") (pintype "bidirectional"))
    )
    (net (code "52") (name "unconnected-(CON1-10:GPIO15(UART_RX)-Pad10)") (class "Default")
      (node (ref "CON1") (pin "10") (pinfunction "10:GPIO15(UART_RX)_10") (pintype "bidirectional"))
    )
    (net (code "53") (name "unconnected-(CON1-19:GPIO10(SPI_MOSI)-Pad19)") (class "Default")
      (node (ref "CON1") (pin "19") (pinfunction "19:GPIO10(SPI_MOSI)_19") (pintype "bidirectional"))
    )
    (net (code "54") (name "unconnected-(CON1-21:GPIO9(SPI_MISO)-Pad21)") (class "Default")
      (node (ref "CON1") (pin "21") (pinfunction "21:GPIO9(SPI_MISO)_21") (pintype "bidirectional"))
    )
    (net (code "55") (name "unconnected-(CON1-23:GPIO11(SPI_CLK)-Pad23)") (class "Default")
      (node (ref "CON1") (pin "23") (pinfunction "23:GPIO11(SPI_CLK)_23") (pintype "bidirectional"))
    )
    (net (code "56") (name "unconnected-(CON1-24:GPIO8(SPI_CE0_N)-Pad24)") (class "Default")
      (node (ref "CON1") (pin "24") (pinfunction "24:GPIO8(SPI_CE0_N)_24") (pintype "bidirectional"))
    )
    (net (code "57") (name "unconnected-(CON1-26:GPIO7(SPI_CE1_N)-Pad26)") (class "Default")
      (node (ref "CON1") (pin "26") (pinfunction "26:GPIO7(SPI_CE1_N)_26") (pintype "bidirectional"))
    )
    (net (code "58") (name "unconnected-(CON1-27:GPIO0(I2C,EEPROM_SDA)-Pad27)") (class "Default")
      (node (ref "CON1") (pin "27") (pinfunction "27:GPIO0(I2C,EEPROM_SDA)_27") (pintype "bidirectional"))
    )
    (net (code "59") (name "unconnected-(CON1-28:GPIO1(I2C,EEPROM_SCL)-Pad28)") (class "Default")
      (node (ref "CON1") (pin "28") (pinfunction "28:GPIO1(I2C,EEPROM_SCL)_28") (pintype "bidirectional"))
    )
    (net (code "60") (name "unconnected-(IC1-LED2-Pad8)") (class "Default")
      (node (ref "IC1") (pin "8") (pinfunction "LED2_8") (pintype "bidirectional"))
    )
    (net (code "61") (name "unconnected-(IC1-LED3-Pad9)") (class "Default")
      (node (ref "IC1") (pin "9") (pinfunction "LED3_9") (pintype "bidirectional"))
    )
    (net (code "62") (name "unconnected-(IC1-LED4-Pad10)") (class "Default")
      (node (ref "IC1") (pin "10") (pinfunction "LED4_10") (pintype "bidirectional"))
    )
    (net (code "63") (name "unconnected-(IC1-LED5-Pad11)") (class "Default")
      (node (ref "IC1") (pin "11") (pinfunction "LED5_11") (pintype "bidirectional"))
    )
    (net (code "64") (name "unconnected-(IC1-LED6-Pad12)") (class "Default")
      (node (ref "IC1") (pin "12") (pinfunction "LED6_12") (pintype "bidirectional"))
    )
    (net (code "65") (name "unconnected-(IC1-LED7-Pad13)") (class "Default")
      (node (ref "IC1") (pin "13") (pinfunction "LED7_13") (pintype "bidirectional"))
    )
    (net (code "66") (name "unconnected-(IC1-LED8-Pad15)") (class "Default")
      (node (ref "IC1") (pin "15") (pinfunction "LED8_15") (pintype "bidirectional"))
    )
    (net (code "67") (name "unconnected-(IC1-LED9-Pad16)") (class "Default")
      (node (ref "IC1") (pin "16") (pinfunction "LED9_16") (pintype "bidirectional"))
    )
    (net (code "68") (name "unconnected-(IC1-LED10-Pad17)") (class "Default")
      (node (ref "IC1") (pin "17") (pinfunction "LED10_17") (pintype "bidirectional"))
    )
    (net (code "69") (name "unconnected-(IC1-LED11-Pad18)") (class "Default")
      (node (ref "IC1") (pin "18") (pinfunction "LED11_18") (pintype "bidirectional"))
    )
    (net (code "70") (name "unconnected-(IC1-LED12-Pad19)") (class "Default")
      (node (ref "IC1") (pin "19") (pinfunction "LED12_19") (pintype "bidirectional"))
    )
    (net (code "71") (name "unconnected-(IC1-LED13-Pad20)") (class "Default")
      (node (ref "IC1") (pin "20") (pinfunction "LED13_20") (pintype "bidirectional"))
    )
    (net (code "72") (name "unconnected-(IC1-LED14-Pad21)") (class "Default")
      (node (ref "IC1") (pin "21") (pinfunction "LED14_21") (pintype "bidirectional"))
    )
    (net (code "73") (name "unconnected-(IC1-LED15-Pad22)") (class "Default")
      (node (ref "IC1") (pin "22") (pinfunction "LED15_22") (pintype "bidirectional"))
    )
    (net (code "74") (name "unconnected-(U2-NC-Pad1)") (class "Default")
      (node (ref "U2") (pin "1") (pinfunction "NC_1") (pintype "bidirectional"))
    )
    (net (code "75") (name "unconnected-(U2-NC-Pad24)") (class "Default")
      (node (ref "U2") (pin "24") (pinfunction "NC_24") (pintype "bidirectional"))
    )
    (net (code "76") (name "unconnected-(U2-NC-Pad30)") (class "Default")
      (node (ref "U2") (pin "30") (pinfunction "NC_30") (pintype "bidirectional"))
    )
  )
)
